# 0185_PG3_LOGIC.net
KiCad netlist of a schematic drawn in Altium Designer
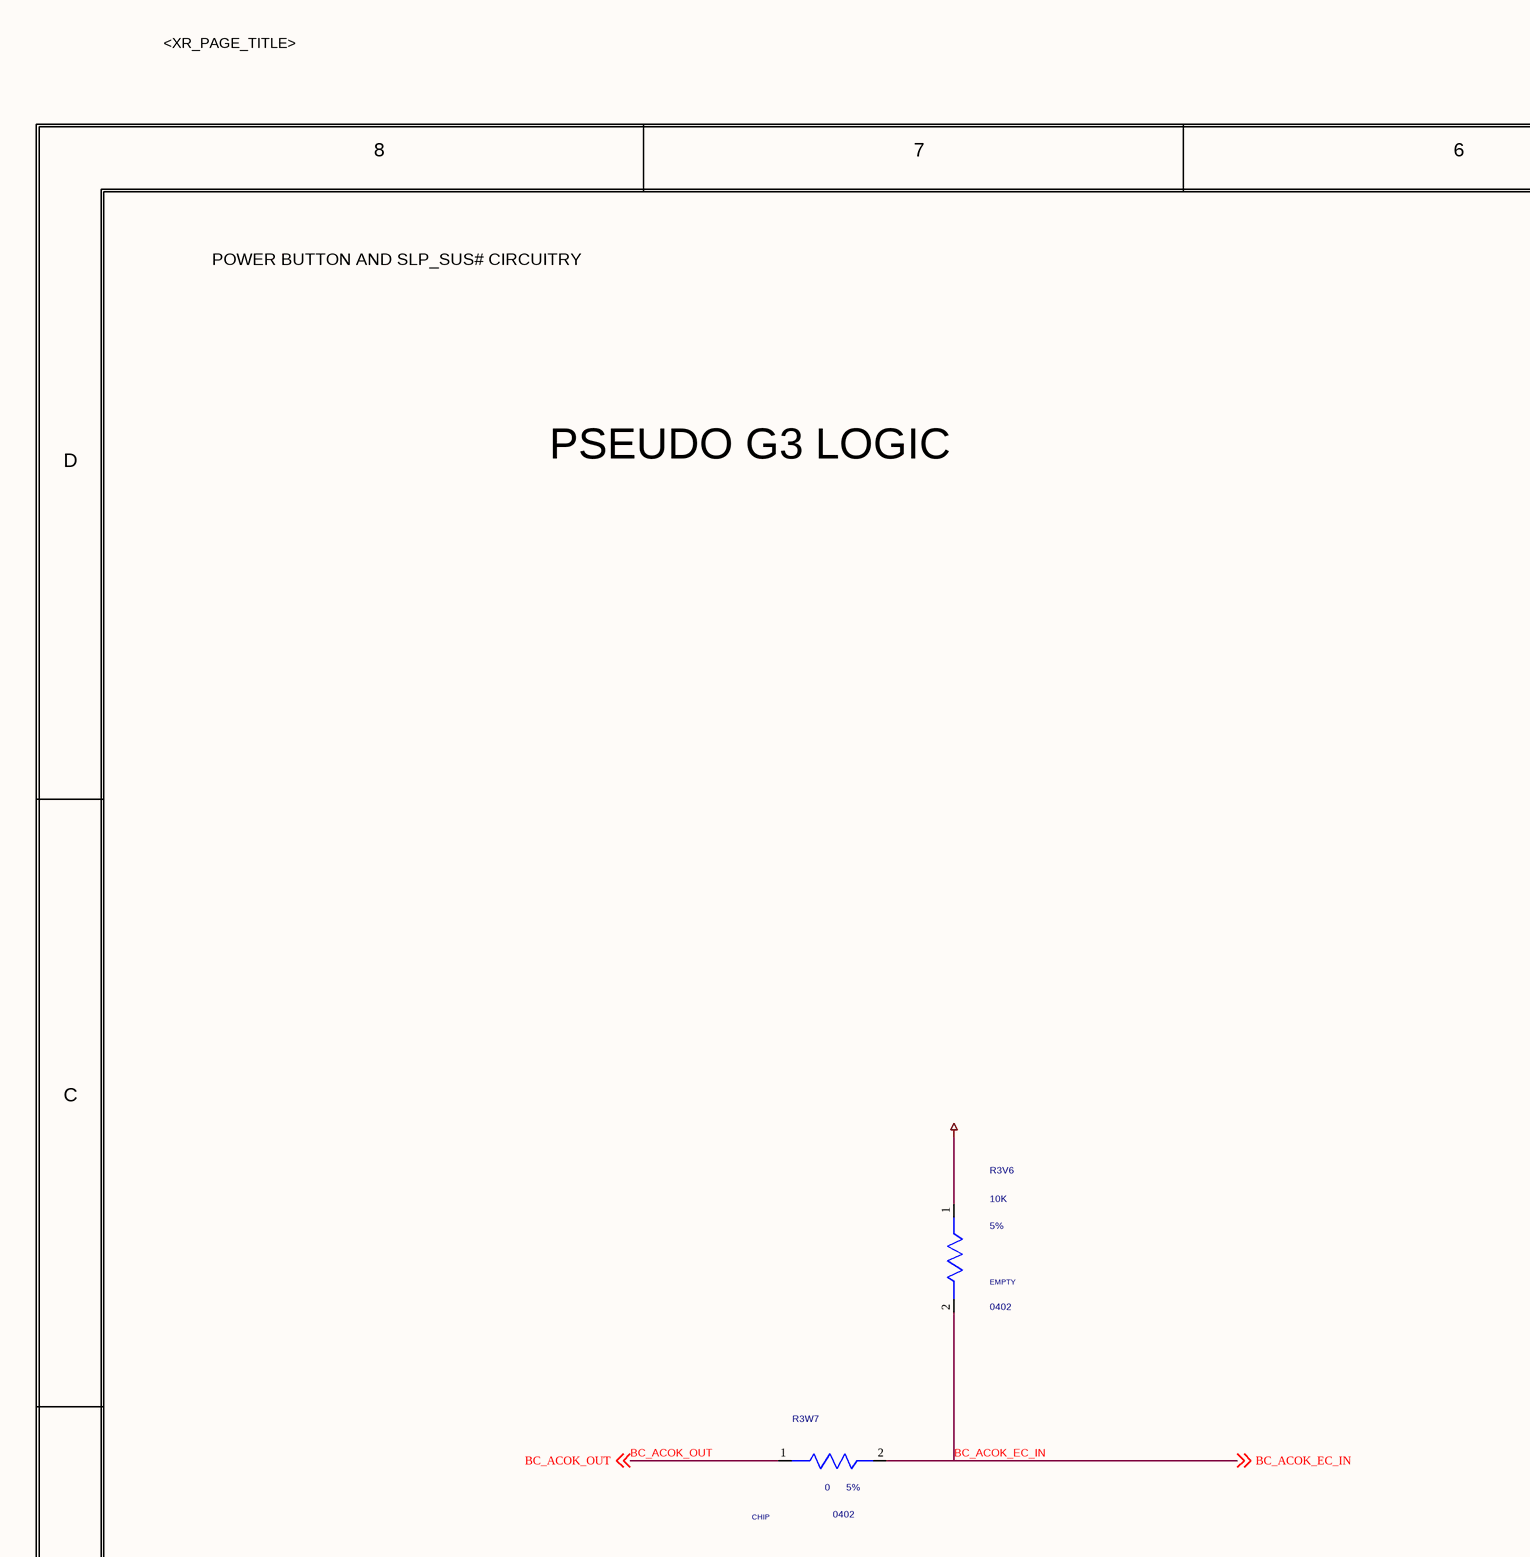
[diagram p0: 0185_PG3 LOGIC.SchDoc, top left]
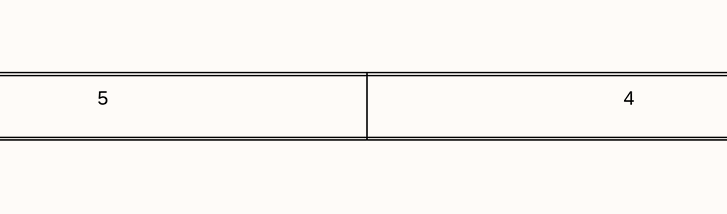
[diagram p1: 0185_PG3 LOGIC.SchDoc, top middle]
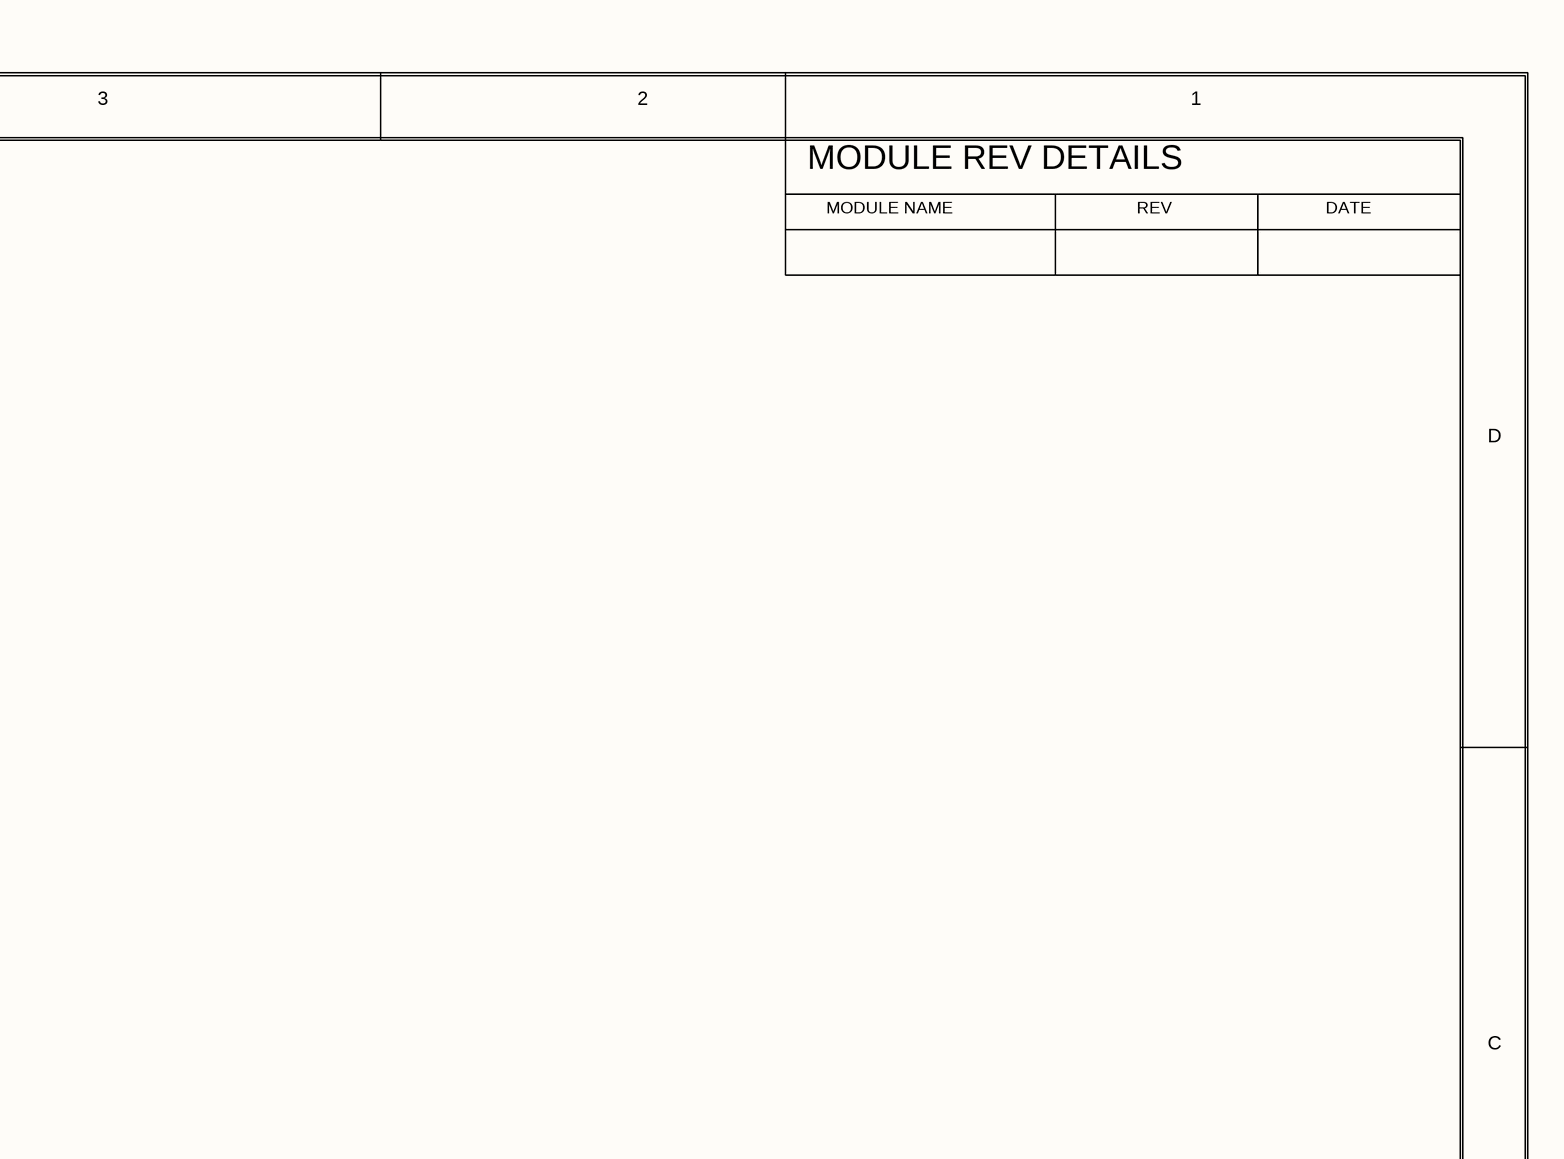
[diagram p2: 0185_PG3 LOGIC.SchDoc, top right]
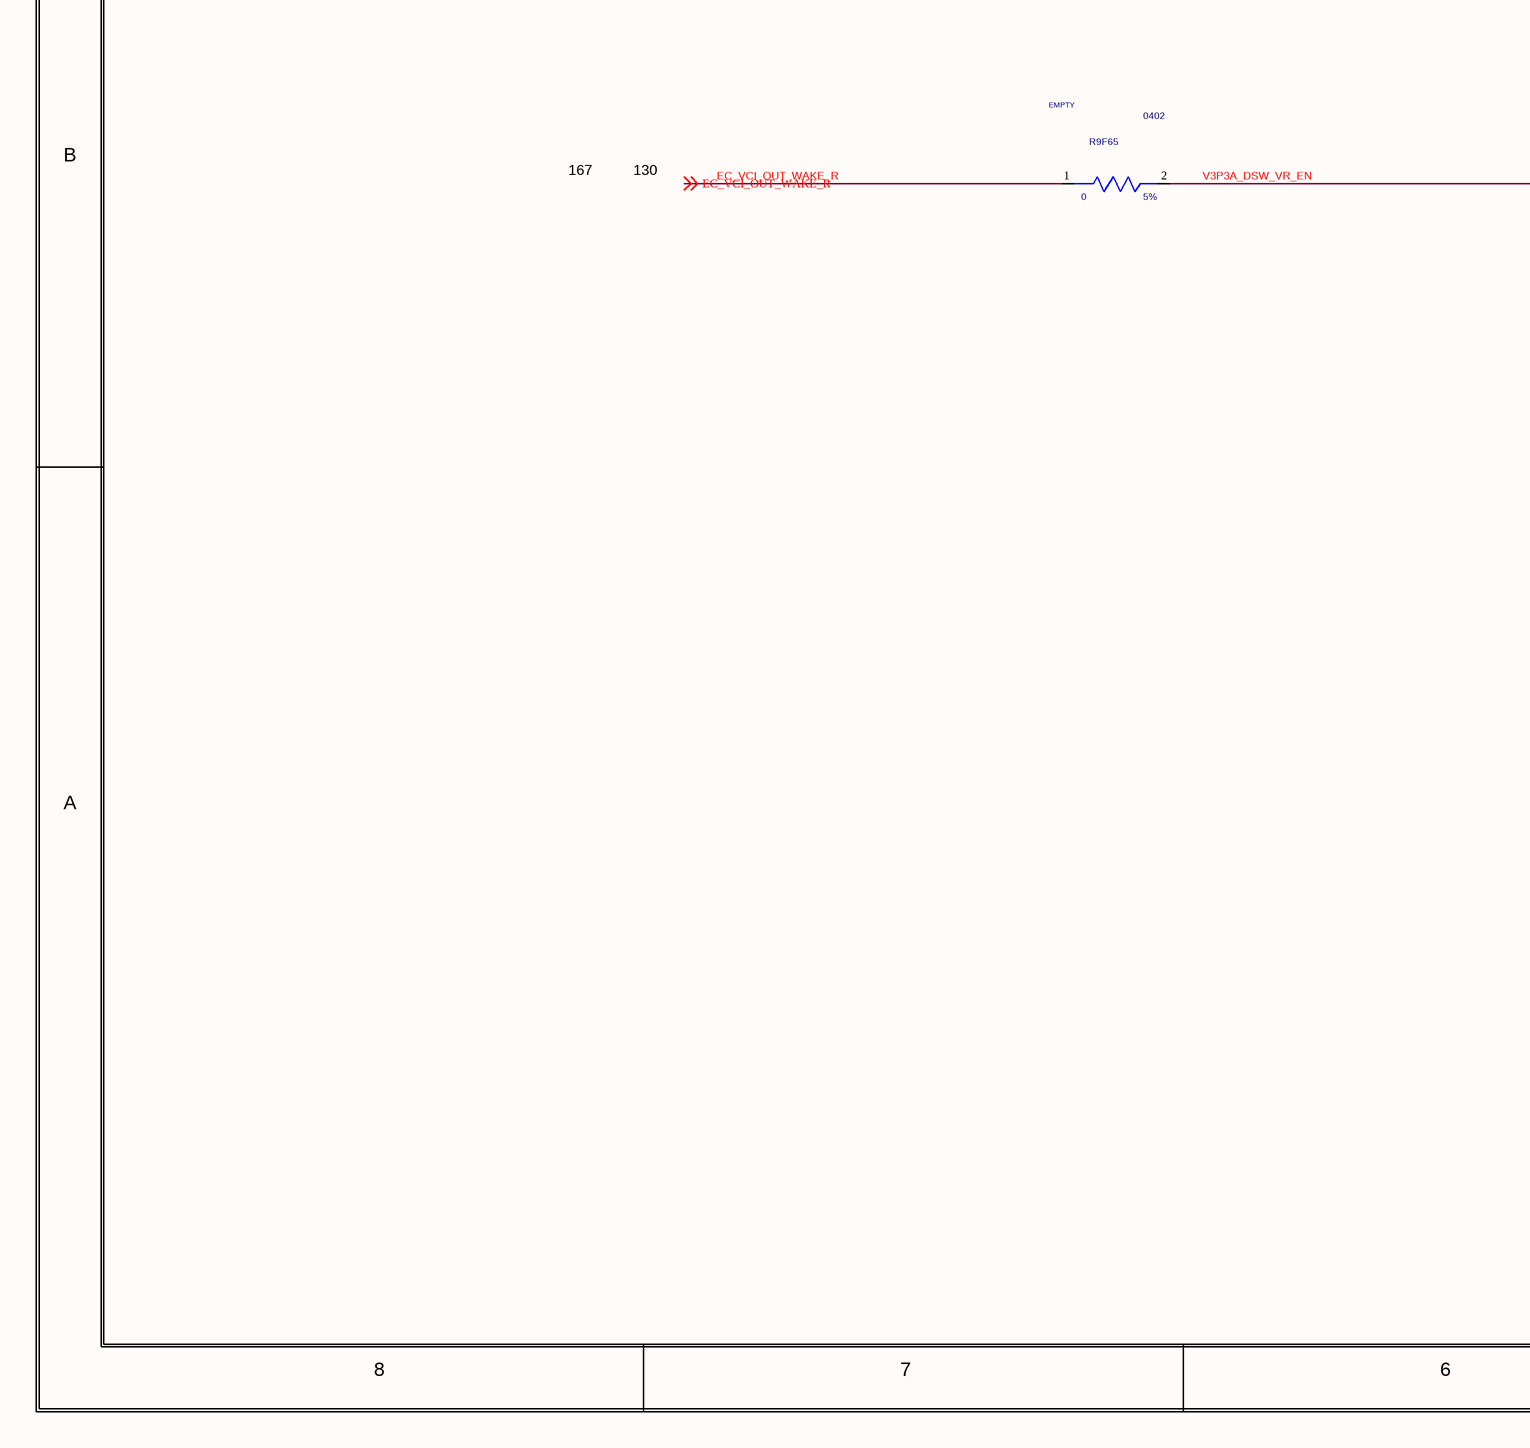
[diagram p3: 0185_PG3 LOGIC.SchDoc, bottom left]
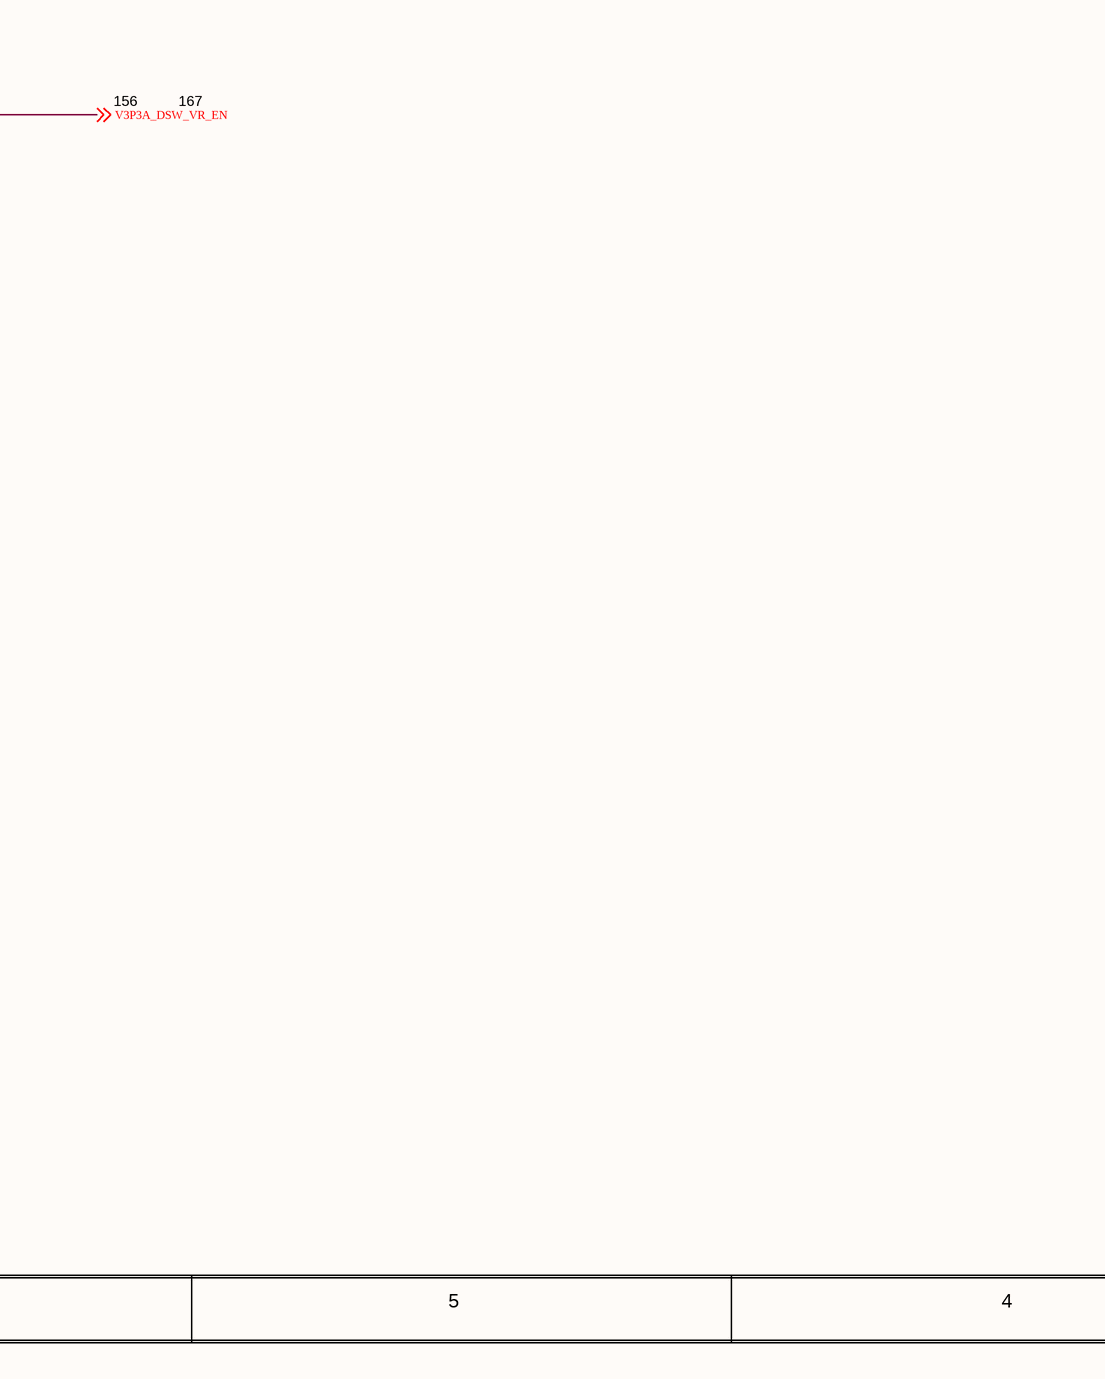
[diagram p4: 0185_PG3 LOGIC.SchDoc, bottom middle]
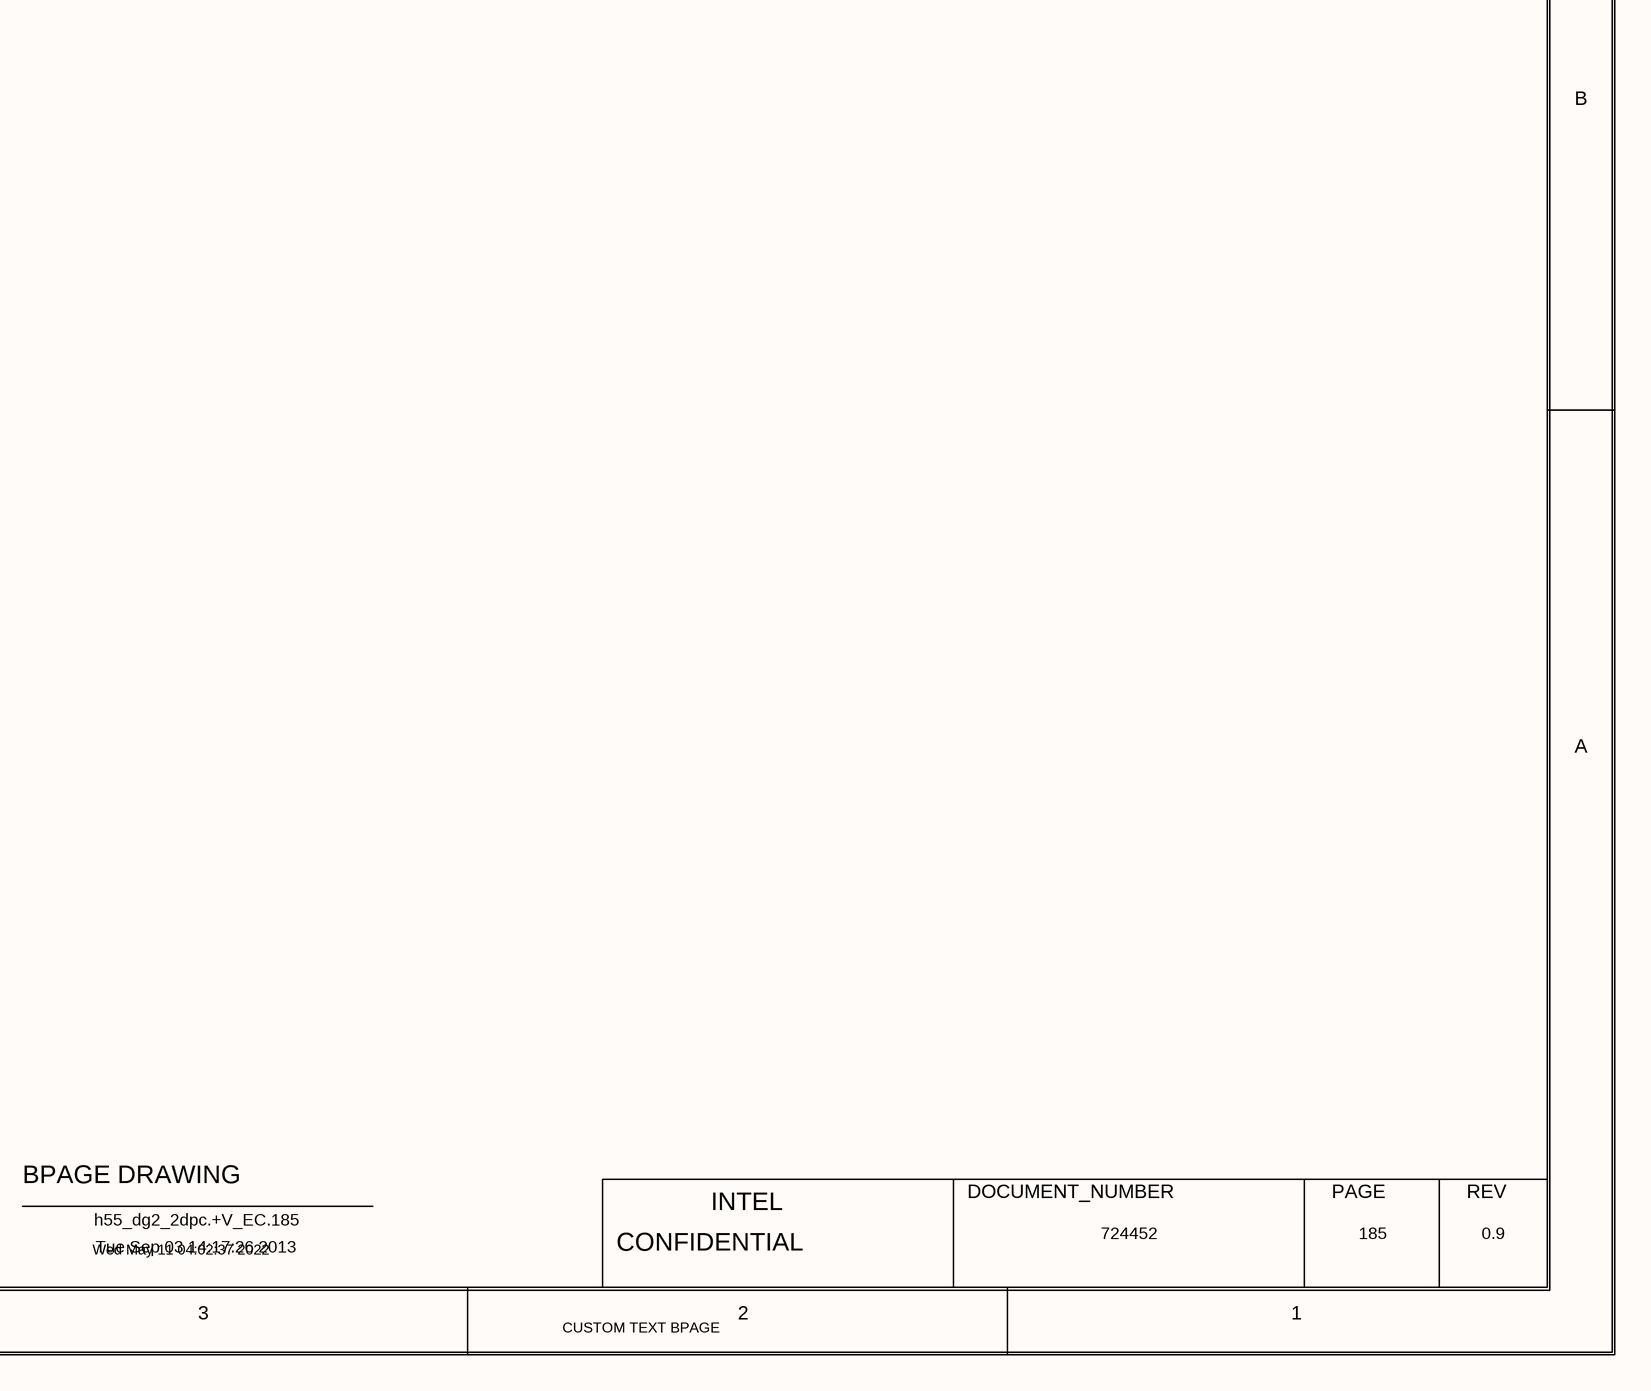
[diagram p5: 0185_PG3 LOGIC.SchDoc, bottom right]

(export (version "E")
  (design (tool "Eeschema 10.0.6"))
  (components
    (comp (ref "R3V6")
      (value "10K")
      (footprint "SMR0402IA")
      (fields
        (field (name "MATERIAL") "EMPTY")
        (field (name "PACK_TYPE") "0402")
        (field (name "PART_NUMBER") "A93549-023")
        (field (name "TOLERANCE") "5%")
      )
      (libsource (lib "*") (part "RES"))
    )
    (comp (ref "R3W7")
      (value "0")
      (footprint "SMR0402IA")
      (fields
        (field (name "MATERIAL") "CHIP")
        (field (name "PACK_TYPE") "0402")
        (field (name "PART_NUMBER") "A93549-001")
        (field (name "TOLERANCE") "5%")
      )
      (libsource (lib "*") (part "RES#1"))
    )
    (comp (ref "R9F65")
      (value "0")
      (footprint "SMR0402IA")
      (fields
        (field (name "MATERIAL") "EMPTY")
        (field (name "PACK_TYPE") "0402")
        (field (name "PART_NUMBER") "A93549-001")
        (field (name "TOLERANCE") "5%")
      )
      (libsource (lib "*") (part "RES#1"))
    )
  )
  (nets
    (net (code "1") (name "+V_EC_VBAT") (class "Default")
      (node (ref "R3V6") (pin "1") (pinfunction "A_1") (pintype "bidirectional"))
    )
    (net (code "2") (name "BC_ACOK_EC_IN") (class "Default")
      (node (ref "R3V6") (pin "2") (pinfunction "B_2") (pintype "bidirectional"))
      (node (ref "R3W7") (pin "2") (pinfunction "B_2") (pintype "bidirectional"))
    )
    (net (code "3") (name "BC_ACOK_OUT") (class "Default")
      (node (ref "R3W7") (pin "1") (pinfunction "A_1") (pintype "bidirectional"))
    )
    (net (code "4") (name "EC_VCI_OUT_WAKE_R") (class "Default")
      (node (ref "R9F65") (pin "1") (pinfunction "A_1") (pintype "bidirectional"))
    )
    (net (code "5") (name "V3P3A_DSW_VR_EN") (class "Default")
      (node (ref "R9F65") (pin "2") (pinfunction "B_2") (pintype "bidirectional"))
    )
  )
)
